# Main_Controller.net
KiCad netlist of a schematic drawn in EAGLE
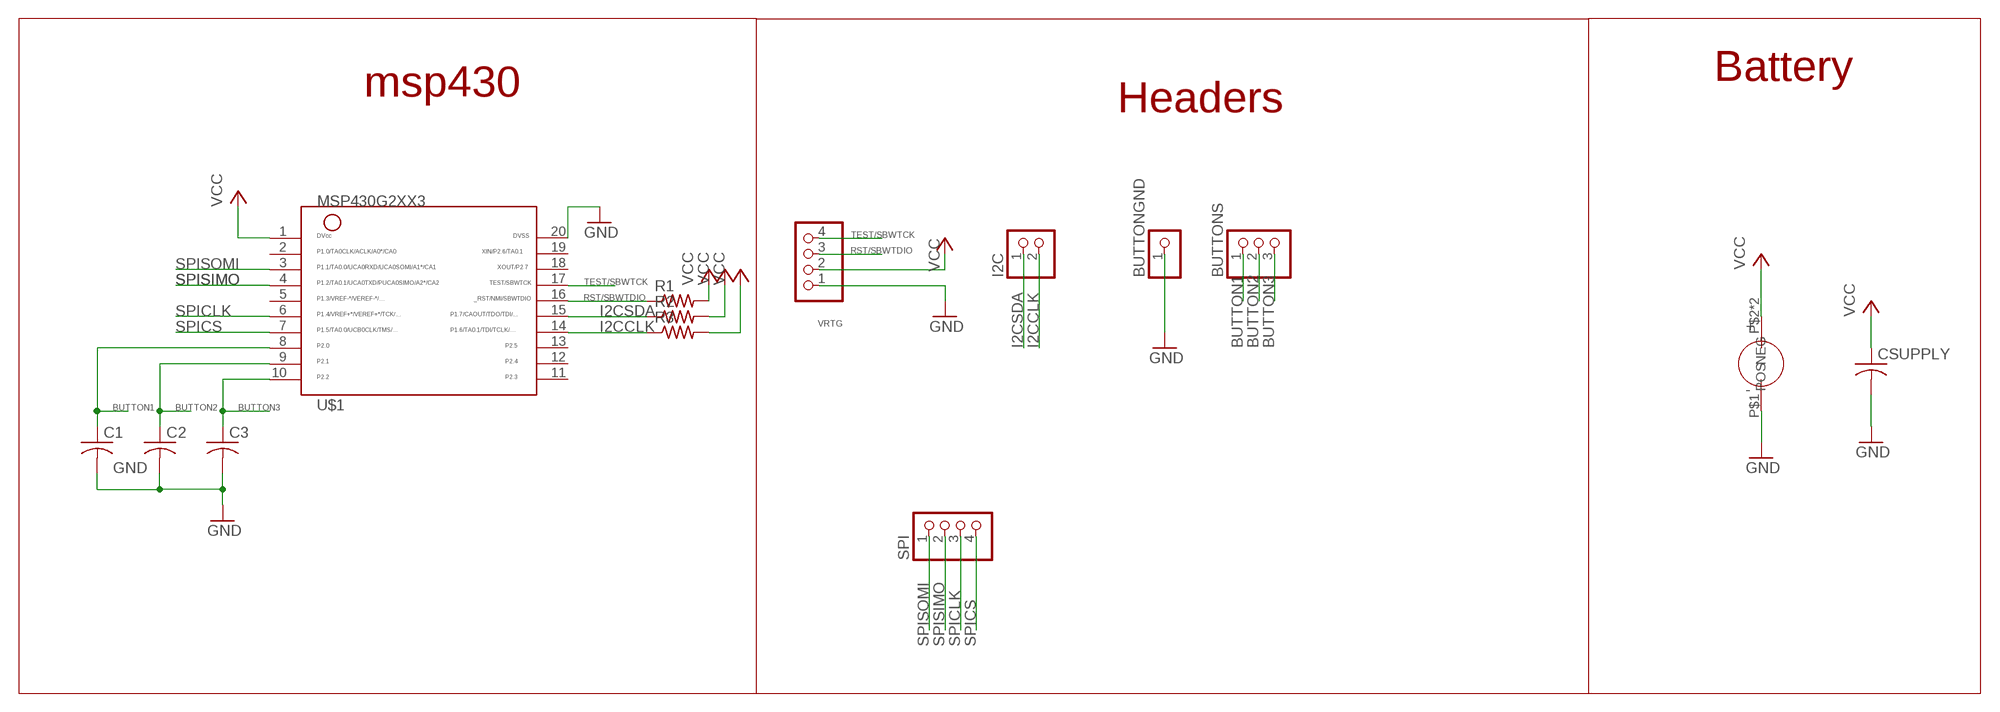
[diagram p0: schematic, sheet 1]

(export (version "E")
  (design (tool "Eeschema 10.0.6"))
  (components
    (comp (ref "BUTTONGND")
      (value "PINHD-1X1")
      (footprint "eagle-import:1X01")
      (libsource (lib "eagle-import") (part "PINHD-1X1"))
    )
    (comp (ref "BUTTONS")
      (value "PINHD-1X3")
      (footprint "eagle-import:1X03")
      (libsource (lib "eagle-import") (part "PINHD-1X3"))
    )
    (comp (ref "C1")
      (value "C-USC1206")
      (footprint "eagle-import:C1206")
      (libsource (lib "eagle-import") (part "C-USC1206"))
    )
    (comp (ref "C2")
      (value "C-USC1206")
      (footprint "eagle-import:C1206")
      (libsource (lib "eagle-import") (part "C-USC1206"))
    )
    (comp (ref "C3")
      (value "C-USC1206")
      (footprint "eagle-import:C1206")
      (libsource (lib "eagle-import") (part "C-USC1206"))
    )
    (comp (ref "CSUPPLY")
      (value "C-USC1206")
      (footprint "eagle-import:C1206")
      (libsource (lib "eagle-import") (part "C-USC1206"))
    )
    (comp (ref "I2C")
      (value "PINHD-1X2")
      (footprint "eagle-import:1X02")
      (libsource (lib "eagle-import") (part "PINHD-1X2"))
    )
    (comp (ref "R1")
      (value "R-US_R1206")
      (footprint "eagle-import:R1206")
      (libsource (lib "eagle-import") (part "R-US_R1206"))
    )
    (comp (ref "R2")
      (value "R-US_R1206")
      (footprint "eagle-import:R1206")
      (libsource (lib "eagle-import") (part "R-US_R1206"))
    )
    (comp (ref "R3")
      (value "R-US_R1206")
      (footprint "eagle-import:R1206")
      (libsource (lib "eagle-import") (part "R-US_R1206"))
    )
    (comp (ref "SPI")
      (value "PINHD-1X4")
      (footprint "eagle-import:1X04")
      (libsource (lib "eagle-import") (part "PINHD-1X4"))
    )
    (comp (ref "U$1")
      (value "MSP430G2XX3TSSOP")
      (footprint "eagle-import:PW20")
      (libsource (lib "eagle-import") (part "MSP430G2XX3TSSOP"))
    )
    (comp (ref "U$2")
      (value "3002BATTERY")
      (footprint "eagle-import:3002BATTERY")
      (libsource (lib "eagle-import") (part "3002BATTERY"))
    )
    (comp (ref "VRTG")
      (value "PINHD-1X4")
      (footprint "eagle-import:1X04")
      (libsource (lib "eagle-import") (part "PINHD-1X4"))
    )
  )
  (nets
    (net (code "1") (name "/BUTTON1") (class "Default")
      (node (ref "BUTTONS") (pin "1") (pinfunction "1_1") (pintype "passive"))
      (node (ref "C1") (pin "1") (pinfunction "1_1") (pintype "passive"))
      (node (ref "U$1") (pin "8") (pinfunction "8_8") (pintype "bidirectional"))
    )
    (net (code "2") (name "/BUTTON2") (class "Default")
      (node (ref "BUTTONS") (pin "2") (pinfunction "2_2") (pintype "passive"))
      (node (ref "C2") (pin "1") (pinfunction "1_1") (pintype "passive"))
      (node (ref "U$1") (pin "9") (pinfunction "9_9") (pintype "bidirectional"))
    )
    (net (code "3") (name "/BUTTON3") (class "Default")
      (node (ref "BUTTONS") (pin "3") (pinfunction "3_3") (pintype "passive"))
      (node (ref "C3") (pin "1") (pinfunction "1_1") (pintype "passive"))
      (node (ref "U$1") (pin "10") (pinfunction "10_10") (pintype "bidirectional"))
    )
    (net (code "4") (name "/I2CCLK") (class "Default")
      (node (ref "I2C") (pin "2") (pinfunction "2_2") (pintype "passive"))
      (node (ref "R3") (pin "1") (pinfunction "1_1") (pintype "passive"))
      (node (ref "U$1") (pin "14") (pinfunction "14_14") (pintype "bidirectional"))
    )
    (net (code "5") (name "/I2CSDA") (class "Default")
      (node (ref "I2C") (pin "1") (pinfunction "1_1") (pintype "passive"))
      (node (ref "R2") (pin "1") (pinfunction "1_1") (pintype "passive"))
      (node (ref "U$1") (pin "15") (pinfunction "15_15") (pintype "bidirectional"))
    )
    (net (code "6") (name "/RST{slash}SBWTDIO") (class "Default")
      (node (ref "R1") (pin "1") (pinfunction "1_1") (pintype "passive"))
      (node (ref "U$1") (pin "16") (pinfunction "16_16") (pintype "bidirectional"))
      (node (ref "VRTG") (pin "3") (pinfunction "3_3") (pintype "passive"))
    )
    (net (code "7") (name "/SPICLK") (class "Default")
      (node (ref "SPI") (pin "3") (pinfunction "3_3") (pintype "passive"))
      (node (ref "U$1") (pin "6") (pinfunction "6_6") (pintype "bidirectional"))
    )
    (net (code "8") (name "/SPICS") (class "Default")
      (node (ref "SPI") (pin "4") (pinfunction "4_4") (pintype "passive"))
      (node (ref "U$1") (pin "7") (pinfunction "7_7") (pintype "bidirectional"))
    )
    (net (code "9") (name "/SPISIMO") (class "Default")
      (node (ref "SPI") (pin "2") (pinfunction "2_2") (pintype "passive"))
      (node (ref "U$1") (pin "4") (pinfunction "4_4") (pintype "bidirectional"))
    )
    (net (code "10") (name "/SPISOMI") (class "Default")
      (node (ref "SPI") (pin "1") (pinfunction "1_1") (pintype "passive"))
      (node (ref "U$1") (pin "3") (pinfunction "3_3") (pintype "bidirectional"))
    )
    (net (code "11") (name "/TEST{slash}SBWTCK") (class "Default")
      (node (ref "U$1") (pin "17") (pinfunction "17_17") (pintype "bidirectional"))
      (node (ref "VRTG") (pin "4") (pinfunction "4_4") (pintype "passive"))
    )
    (net (code "12") (name "GND") (class "Default")
      (node (ref "BUTTONGND") (pin "1") (pinfunction "1_1") (pintype "passive"))
      (node (ref "C1") (pin "2") (pinfunction "2_2") (pintype "passive"))
      (node (ref "C2") (pin "2") (pinfunction "2_2") (pintype "passive"))
      (node (ref "C3") (pin "2") (pinfunction "2_2") (pintype "passive"))
      (node (ref "CSUPPLY") (pin "2") (pinfunction "2_2") (pintype "passive"))
      (node (ref "U$1") (pin "20") (pinfunction "20_20") (pintype "bidirectional"))
      (node (ref "U$2") (pin "P$1") (pinfunction "NEG_P$1") (pintype "bidirectional"))
      (node (ref "VRTG") (pin "1") (pinfunction "1_1") (pintype "passive"))
    )
    (net (code "13") (name "VCC") (class "Default")
      (node (ref "CSUPPLY") (pin "1") (pinfunction "1_1") (pintype "passive"))
      (node (ref "R1") (pin "2") (pinfunction "2_2") (pintype "passive"))
      (node (ref "R2") (pin "2") (pinfunction "2_2") (pintype "passive"))
      (node (ref "R3") (pin "2") (pinfunction "2_2") (pintype "passive"))
      (node (ref "U$1") (pin "1") (pinfunction "1_1") (pintype "bidirectional"))
      (node (ref "U$2") (pin "P$2") (pinfunction "POS_P$2") (pintype "bidirectional"))
      (node (ref "U$2") (pin "P$3") (pinfunction "POS_P$3") (pintype "bidirectional"))
      (node (ref "VRTG") (pin "2") (pinfunction "2_2") (pintype "passive"))
    )
    (net (code "14") (name "unconnected-(U$1-Pad2)") (class "Default")
      (node (ref "U$1") (pin "2") (pinfunction "2_2") (pintype "bidirectional"))
    )
    (net (code "15") (name "unconnected-(U$1-Pad5)") (class "Default")
      (node (ref "U$1") (pin "5") (pinfunction "5_5") (pintype "bidirectional"))
    )
    (net (code "16") (name "unconnected-(U$1-Pad11)") (class "Default")
      (node (ref "U$1") (pin "11") (pinfunction "11_11") (pintype "bidirectional"))
    )
    (net (code "17") (name "unconnected-(U$1-Pad12)") (class "Default")
      (node (ref "U$1") (pin "12") (pinfunction "12_12") (pintype "bidirectional"))
    )
    (net (code "18") (name "unconnected-(U$1-Pad13)") (class "Default")
      (node (ref "U$1") (pin "13") (pinfunction "13_13") (pintype "bidirectional"))
    )
    (net (code "19") (name "unconnected-(U$1-Pad18)") (class "Default")
      (node (ref "U$1") (pin "18") (pinfunction "18_18") (pintype "bidirectional"))
    )
    (net (code "20") (name "unconnected-(U$1-Pad19)") (class "Default")
      (node (ref "U$1") (pin "19") (pinfunction "19_19") (pintype "bidirectional"))
    )
  )
)
